# Z_-.net
KiCad netlist of a schematic drawn in EAGLE
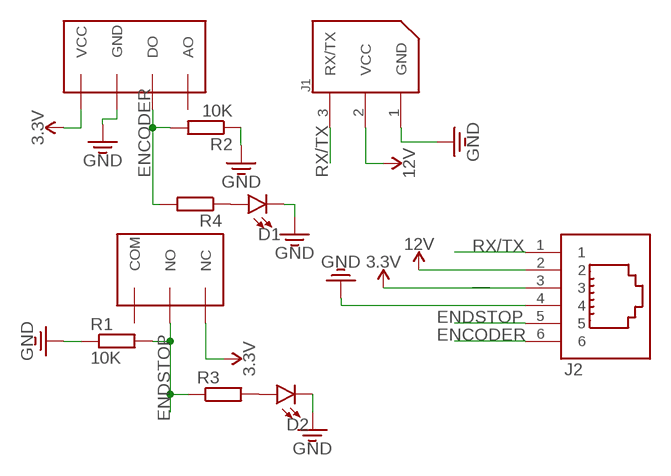
[diagram p0: schematic, sheet 1]

(export (version "E")
  (design (tool "Eeschema 10.0.6"))
  (components
    (comp (ref "D1")
      (value "LED5MM")
      (footprint "eagle-import:LED_5MM")
      (libsource (lib "eagle-import") (part "LED5MM"))
    )
    (comp (ref "D2")
      (value "LED5MM")
      (footprint "eagle-import:LED_5MM")
      (libsource (lib "eagle-import") (part "LED5MM"))
    )
    (comp (ref "J1")
      (value "22-03-5035")
      (footprint "eagle-import:5267-3")
      (libsource (lib "eagle-import") (part "22-03-5035"))
    )
    (comp (ref "J2")
      (value "615006138421")
      (footprint "eagle-import:615006138421")
      (libsource (lib "eagle-import") (part "615006138421"))
    )
    (comp (ref "R1")
      (value "10K")
      (footprint "eagle-import:0204_7")
      (libsource (lib "eagle-import") (part "R-EU_0204/7"))
    )
    (comp (ref "R2")
      (value "10K")
      (footprint "eagle-import:0204_7")
      (libsource (lib "eagle-import") (part "R-EU_0204/7"))
    )
    (comp (ref "R3")
      (value "R-EU_0204/7")
      (footprint "eagle-import:0204_7")
      (libsource (lib "eagle-import") (part "R-EU_0204/7"))
    )
    (comp (ref "R4")
      (value "R-EU_0204/7")
      (footprint "eagle-import:0204_7")
      (libsource (lib "eagle-import") (part "R-EU_0204/7"))
    )
    (comp (ref "U$1")
      (value "OPTICAL_ENCODER_FC-01")
      (footprint "eagle-import:OPTICAL_ENCODER_FC-01")
      (libsource (lib "eagle-import") (part "OPTICAL_ENCODER_FC-01"))
    )
    (comp (ref "U$2")
      (value "ENDSTOP")
      (footprint "eagle-import:ENDSTOP")
      (libsource (lib "eagle-import") (part "ENDSTOP"))
    )
  )
  (nets
    (net (code "1") (name "/ENCODER") (class "Default")
      (node (ref "J2") (pin "6") (pinfunction "6_6") (pintype "passive"))
      (node (ref "R2") (pin "2") (pinfunction "2_2") (pintype "passive"))
      (node (ref "R4") (pin "2") (pinfunction "2_2") (pintype "passive"))
      (node (ref "U$1") (pin "DO") (pinfunction "DO_DO") (pintype "bidirectional"))
    )
    (net (code "2") (name "/ENDSTOP") (class "Default")
      (node (ref "J2") (pin "5") (pinfunction "5_5") (pintype "passive"))
      (node (ref "R1") (pin "2") (pinfunction "2_2") (pintype "passive"))
      (node (ref "R3") (pin "1") (pinfunction "1_1") (pintype "passive"))
      (node (ref "U$2") (pin "NO") (pinfunction "NO_NO") (pintype "bidirectional"))
    )
    (net (code "3") (name "/RX{slash}TX") (class "Default")
      (node (ref "J1") (pin "3") (pinfunction "RX/TX_3") (pintype "bidirectional"))
      (node (ref "J2") (pin "1") (pinfunction "1_1") (pintype "passive"))
    )
    (net (code "4") (name "3.3V") (class "Default")
      (node (ref "J2") (pin "3") (pinfunction "3_3") (pintype "passive"))
      (node (ref "U$1") (pin "VCC") (pinfunction "VCC_VCC") (pintype "bidirectional"))
      (node (ref "U$2") (pin "NC") (pinfunction "NC_NC") (pintype "bidirectional"))
    )
    (net (code "5") (name "12V") (class "Default")
      (node (ref "J1") (pin "2") (pinfunction "VCC_2") (pintype "bidirectional"))
      (node (ref "J2") (pin "2") (pinfunction "2_2") (pintype "passive"))
    )
    (net (code "6") (name "GND") (class "Default")
      (node (ref "D1") (pin "K") (pinfunction "C_K") (pintype "passive"))
      (node (ref "D2") (pin "K") (pinfunction "C_K") (pintype "passive"))
      (node (ref "J1") (pin "1") (pinfunction "GND_1") (pintype "bidirectional"))
      (node (ref "J2") (pin "4") (pinfunction "4_4") (pintype "passive"))
      (node (ref "R1") (pin "1") (pinfunction "1_1") (pintype "passive"))
      (node (ref "R2") (pin "1") (pinfunction "1_1") (pintype "passive"))
      (node (ref "U$1") (pin "GND") (pinfunction "GND_GND") (pintype "bidirectional"))
    )
    (net (code "7") (name "Net-(D1-PadA)") (class "Default")
      (node (ref "D1") (pin "A") (pinfunction "A_A") (pintype "passive"))
      (node (ref "R4") (pin "1") (pinfunction "1_1") (pintype "passive"))
    )
    (net (code "8") (name "Net-(D2-PadA)") (class "Default")
      (node (ref "D2") (pin "A") (pinfunction "A_A") (pintype "passive"))
      (node (ref "R3") (pin "2") (pinfunction "2_2") (pintype "passive"))
    )
    (net (code "9") (name "unconnected-(U$1-PadAO)") (class "Default")
      (node (ref "U$1") (pin "AO") (pinfunction "AO_AO") (pintype "bidirectional"))
    )
    (net (code "10") (name "unconnected-(U$2-PadCOM)") (class "Default")
      (node (ref "U$2") (pin "COM") (pinfunction "COM_COM") (pintype "bidirectional"))
    )
  )
)
